# 13_MRAM_RTC_WDT.net
KiCad netlist of a schematic drawn in Altium Designer
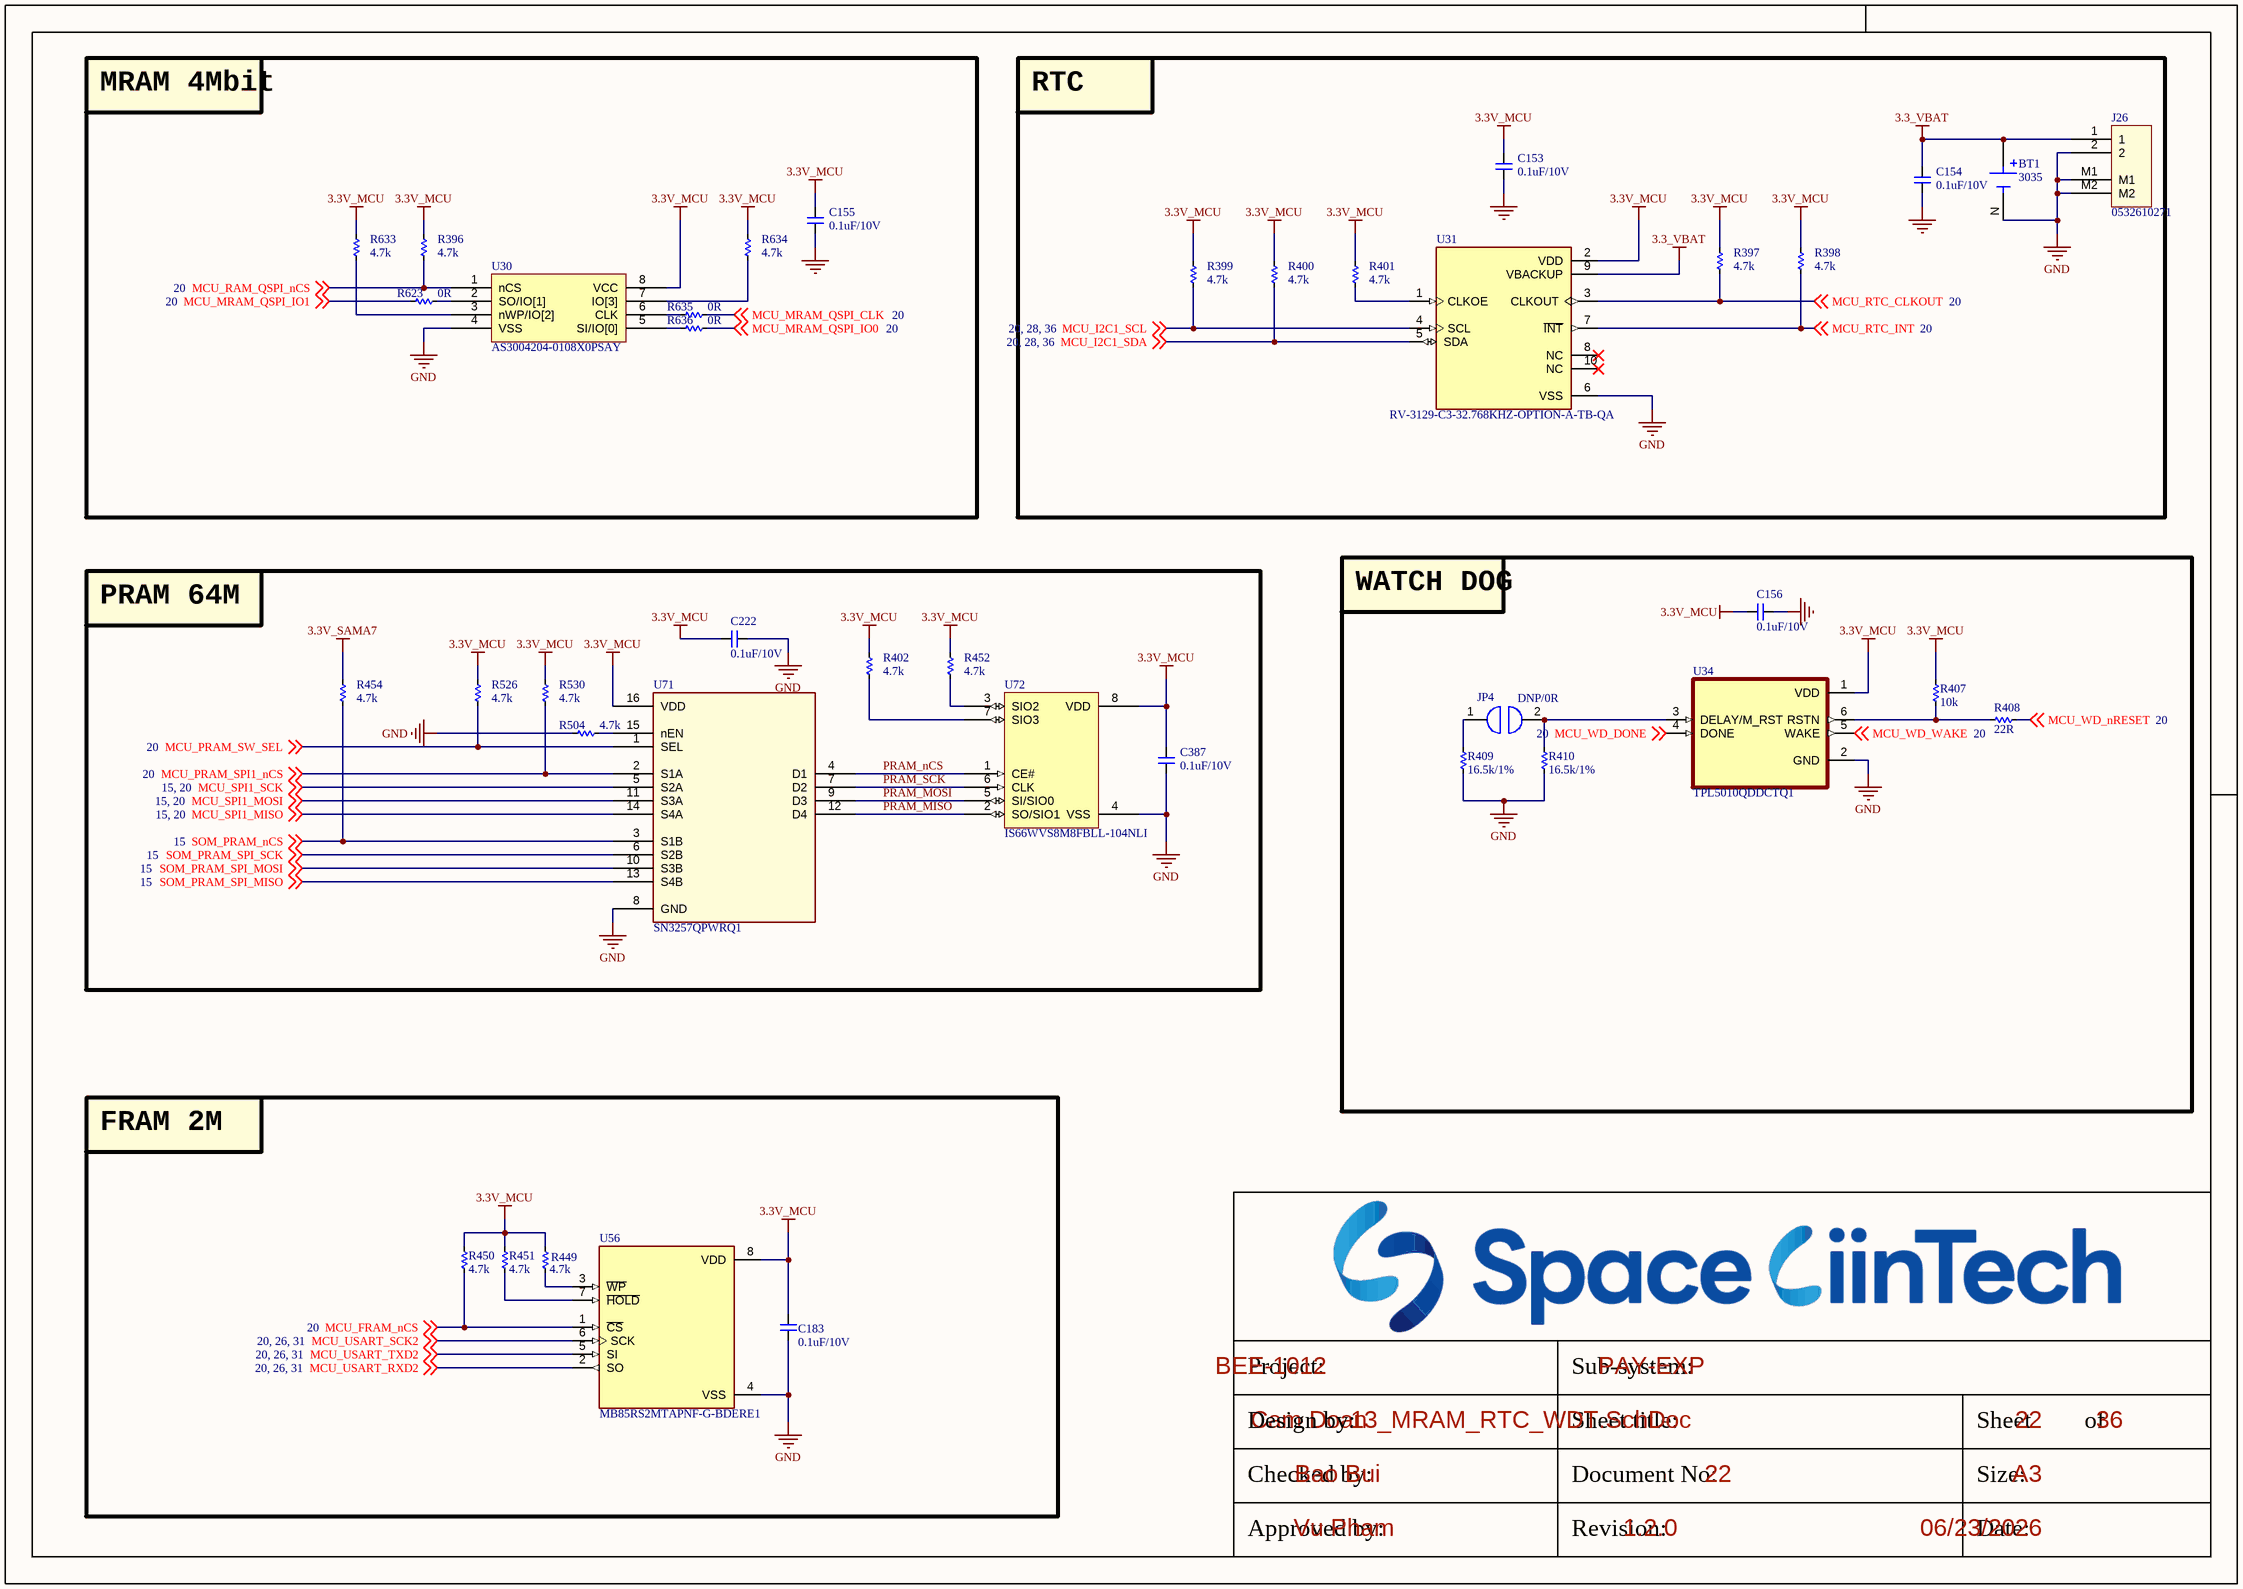
[diagram p0: 13_MRAM_RTC_WDT.SchDoc]

(export (version "E")
  (design (tool "Eeschema 10.0.6"))
  (components
    (comp (ref "BT1")
      (value "3035")
      (footprint "BAT_3035")
      (description "Battery Clip; THM; 20mm Cell; PhosBronze/Nickel ¦ Keystone Electronics 3035")
      (fields (field (name "MF") "Keystone Electronics"))
      (libsource (lib "LABLIB") (part "BT_HOLDER_3035"))
    )
    (comp (ref "C153")
      (value "0.1uF/10V")
      (footprint "CAP_C_1005X60")
      (description "CAP")
      (libsource (lib "LABLIB") (part "_CAP_C_2"))
    )
    (comp (ref "C154")
      (value "0.1uF/10V")
      (footprint "CAP_C_1005X60")
      (description "CAP")
      (libsource (lib "LABLIB") (part "_CAP_C_2"))
    )
    (comp (ref "C155")
      (value "0.1uF/10V")
      (footprint "CAP_C_1005X60")
      (description "CAP")
      (libsource (lib "LABLIB") (part "_CAP_C_2"))
    )
    (comp (ref "C156")
      (value "0.1uF/10V")
      (footprint "CAP_C_1005X60")
      (description "CAP")
      (libsource (lib "LABLIB") (part "_CAP_C_2"))
    )
    (comp (ref "C183")
      (value "0.1uF/10V")
      (footprint "CAP_C_1005X60")
      (description "CAP CHIP")
      (libsource (lib "LABLIB") (part "_CAP_C_2"))
    )
    (comp (ref "C222")
      (value "0.1uF/10V")
      (footprint "CAP_C_1005X60")
      (description "CAP")
      (libsource (lib "LABLIB") (part "_CAP_C_2"))
    )
    (comp (ref "C387")
      (value "0.1uF/10V")
      (footprint "CAP_C_1005X60")
      (description "CAP")
      (libsource (lib "LABLIB") (part "_CAP_C_2"))
    )
    (comp (ref "J26")
      (value "0532610271")
      (footprint "molex_0532610271")
      (libsource (lib "LABLIB") (part "Header 2x1_2M"))
    )
    (comp (ref "JP4") (value "DNP/0R") (footprint "JUMPER_1608") (libsource (lib "EXP_V1") (part "JUMPER")))
    (comp (ref "R396")
      (value "4.7k")
      (footprint "RES_C_1005X40")
      (description "RES")
      (libsource (lib "LABLIB") (part "_RES_B_2"))
    )
    (comp (ref "R397")
      (value "4.7k")
      (footprint "RES_C_1005X40")
      (description "RES")
      (libsource (lib "LABLIB") (part "_RES_B_2"))
    )
    (comp (ref "R398")
      (value "4.7k")
      (footprint "RES_C_1005X40")
      (description "RES")
      (libsource (lib "LABLIB") (part "_RES_B_2"))
    )
    (comp (ref "R399")
      (value "4.7k")
      (footprint "RES_C_1005X40")
      (description "RES")
      (libsource (lib "LABLIB") (part "_RES_B_2"))
    )
    (comp (ref "R400")
      (value "4.7k")
      (footprint "RES_C_1005X40")
      (description "RES")
      (libsource (lib "LABLIB") (part "_RES_B_2"))
    )
    (comp (ref "R401")
      (value "4.7k")
      (footprint "RES_C_1005X40")
      (description "RES")
      (libsource (lib "LABLIB") (part "_RES_B_2"))
    )
    (comp (ref "R402")
      (value "4.7k")
      (footprint "RES_C_1005X40")
      (description "RES")
      (libsource (lib "LABLIB") (part "_RES_B_2"))
    )
    (comp (ref "R407")
      (value "10k")
      (footprint "RES_C_1005X40")
      (description "RES")
      (libsource (lib "LABLIB") (part "_RES_B_2"))
    )
    (comp (ref "R408")
      (value "22R")
      (footprint "RES_C_1005X40")
      (description "RES")
      (libsource (lib "LABLIB") (part "_RES_B_2"))
    )
    (comp (ref "R409")
      (value "16.5k/1%")
      (footprint "RES_C_1005X40")
      (description "RES")
      (libsource (lib "LABLIB") (part "_RES_B_2"))
    )
    (comp (ref "R410")
      (value "16.5k/1%")
      (footprint "RES_C_1005X40")
      (description "RES")
      (libsource (lib "LABLIB") (part "_RES_B_2"))
    )
    (comp (ref "R449")
      (value "4.7k")
      (footprint "RES_C_1005X40")
      (description "RES")
      (libsource (lib "LABLIB") (part "_RES_B_2"))
    )
    (comp (ref "R450")
      (value "4.7k")
      (footprint "RES_C_1005X40")
      (description "RES")
      (libsource (lib "LABLIB") (part "_RES_B_2"))
    )
    (comp (ref "R451")
      (value "4.7k")
      (footprint "RES_C_1005X40")
      (description "RES")
      (libsource (lib "LABLIB") (part "_RES_B_2"))
    )
    (comp (ref "R452")
      (value "4.7k")
      (footprint "RES_C_1005X40")
      (description "RES")
      (libsource (lib "LABLIB") (part "_RES_B_2"))
    )
    (comp (ref "R454")
      (value "4.7k")
      (footprint "RES_C_1005X40")
      (description "RES")
      (libsource (lib "LABLIB") (part "_RES_B_2"))
    )
    (comp (ref "R504")
      (value "4.7k")
      (footprint "RES_C_1005X40")
      (description "RES")
      (libsource (lib "LABLIB") (part "_RES_B_2"))
    )
    (comp (ref "R526")
      (value "4.7k")
      (footprint "RES_C_1005X40")
      (description "RES")
      (libsource (lib "LABLIB") (part "_RES_B_2"))
    )
    (comp (ref "R530")
      (value "4.7k")
      (footprint "RES_C_1005X40")
      (description "RES")
      (libsource (lib "LABLIB") (part "_RES_B_2"))
    )
    (comp (ref "R623")
      (value "0R")
      (footprint "RES_C_1005X40")
      (description "RES")
      (libsource (lib "LABLIB") (part "_RES_B_2"))
    )
    (comp (ref "R633")
      (value "4.7k")
      (footprint "RES_C_1005X40")
      (description "RES")
      (libsource (lib "LABLIB") (part "_RES_B_2"))
    )
    (comp (ref "R634")
      (value "4.7k")
      (footprint "RES_C_1005X40")
      (description "RES")
      (libsource (lib "LABLIB") (part "_RES_B_2"))
    )
    (comp (ref "R635")
      (value "0R")
      (footprint "RES_C_1005X40")
      (description "RES")
      (libsource (lib "LABLIB") (part "_RES_B_2"))
    )
    (comp (ref "R636")
      (value "0R")
      (footprint "RES_C_1005X40")
      (description "RES")
      (libsource (lib "LABLIB") (part "_RES_B_2"))
    )
    (comp (ref "U30")
      (value "AS3004204-0108X0PSAY")
      (footprint "SOIC127P790X216-8")
      (libsource (lib "LABLIB") (part "IC_RAM_AS3004204-0108X0PSAY"))
    )
    (comp (ref "U31")
      (value "RV-3129-C3-32.768KHZ-OPTION-A-TB-QA")
      (footprint "IC_RV-3129-C3_32.768KHZ_OPTION_A_TB_QA")
      (description "Real-Time Clock Module, Temperature compensated, in 2.5 x 3.7 mm package")
      (fields (field (name "MF") "Micro Crystal") (field (name "MP") "RV-3129-C3 32.768KHZ OPTION A TB QA"))
      (libsource (lib "RV-3129-C3_32.768KHZ_OPTION_A_TB_QA") (part "RV-3129-C3_32.768KHZ_OPTION_A_TB_QA"))
    )
    (comp (ref "U34")
      (value "TPL5010QDDCTQ1")
      (footprint "SOT95P280X145-6N")
      (libsource (lib "TPL5010QDDCTQ1") (part "TPL5010QDDCTQ1"))
    )
    (comp (ref "U56")
      (value "MB85RS2MTAPNF-G-BDERE1")
      (footprint "SOIC127P602X173-8N")
      (description "FRAM _Ferroelectric RAM_ Memory IC 2Mb _256K x 8_ SPI 40MHz 8-SOP")
      (fields (field (name "MF") "Fujitsu Electronics") (field (name "DIGI-KEY_PART_NUMBER") "865-1286-1-ND"))
      (libsource (lib "MB85RS2MTAPNF-G-BDERE1") (part "MB85RS2MTAPNF-G-BDERE1"))
    )
    (comp (ref "U71")
      (value "SN3257QPWRQ1")
      (footprint "SOIC_PRQ1_TEX")
      (fields (field (name "COPYRIGHT") "Copyright (C) 2025 Ultra Librarian. All rights reserved."))
      (libsource (lib "LABLIB") (part "IC_SW_SPI_SN3257QPWRQ1"))
    )
    (comp (ref "U72")
      (value "IS66WVS8M8FBLL-104NLI")
      (footprint "SOIC8_150MIL_N_ISI")
      (description "No Description Available")
      (fields
        (field (name "MANUFACTURER_PART_NUMBER") "IS66WVS4M8BLL-104NLI")
        (field (name "COPYRIGHT") "Copyright (C) 2025 Ultra Librarian. All rights reserved.")
      )
      (libsource (lib "LABLIB") (part "IS66WVS4M8BLL-104NLI"))
    )
  )
  (nets
    (net (code "1") (name "/PRAM_MISO") (class "Default")
      (node (ref "U71") (pin "12") (pinfunction "D4_12") (pintype "passive"))
      (node (ref "U72") (pin "2") (pinfunction "SO/SIO1_2") (pintype "bidirectional"))
    )
    (net (code "2") (name "/PRAM_MOSI") (class "Default")
      (node (ref "U71") (pin "9") (pinfunction "D3_9") (pintype "passive"))
      (node (ref "U72") (pin "5") (pinfunction "SI/SIO0_5") (pintype "bidirectional"))
    )
    (net (code "3") (name "/PRAM_SCK") (class "Default")
      (node (ref "U71") (pin "7") (pinfunction "D2_7") (pintype "passive"))
      (node (ref "U72") (pin "6") (pinfunction "CLK_6") (pintype "input"))
    )
    (net (code "4") (name "/PRAM_nCS") (class "Default")
      (node (ref "U71") (pin "4") (pinfunction "D1_4") (pintype "passive"))
      (node (ref "U72") (pin "1") (pinfunction "CE#_1") (pintype "input"))
    )
    (net (code "5") (name "3.3V_MCU") (class "Default")
      (node (ref "C153") (pin "2") (pinfunction "2_2") (pintype "passive"))
      (node (ref "C155") (pin "2") (pinfunction "2_2") (pintype "passive"))
      (node (ref "C156") (pin "2") (pinfunction "2_2") (pintype "passive"))
      (node (ref "C183") (pin "2") (pinfunction "2_2") (pintype "passive"))
      (node (ref "C222") (pin "1") (pinfunction "1_1") (pintype "passive"))
      (node (ref "C387") (pin "1") (pinfunction "1_1") (pintype "passive"))
      (node (ref "R396") (pin "2") (pinfunction "2_2") (pintype "passive"))
      (node (ref "R397") (pin "2") (pinfunction "2_2") (pintype "passive"))
      (node (ref "R398") (pin "2") (pinfunction "2_2") (pintype "passive"))
      (node (ref "R399") (pin "2") (pinfunction "2_2") (pintype "passive"))
      (node (ref "R400") (pin "2") (pinfunction "2_2") (pintype "passive"))
      (node (ref "R401") (pin "1") (pinfunction "1_1") (pintype "passive"))
      (node (ref "R402") (pin "2") (pinfunction "2_2") (pintype "passive"))
      (node (ref "R407") (pin "2") (pinfunction "2_2") (pintype "passive"))
      (node (ref "R449") (pin "2") (pinfunction "2_2") (pintype "passive"))
      (node (ref "R450") (pin "2") (pinfunction "2_2") (pintype "passive"))
      (node (ref "R451") (pin "2") (pinfunction "2_2") (pintype "passive"))
      (node (ref "R452") (pin "2") (pinfunction "2_2") (pintype "passive"))
      (node (ref "R526") (pin "2") (pinfunction "2_2") (pintype "passive"))
      (node (ref "R530") (pin "2") (pinfunction "2_2") (pintype "passive"))
      (node (ref "R633") (pin "2") (pinfunction "2_2") (pintype "passive"))
      (node (ref "R634") (pin "2") (pinfunction "2_2") (pintype "passive"))
      (node (ref "U30") (pin "8") (pinfunction "VCC_8") (pintype "passive"))
      (node (ref "U31") (pin "2") (pinfunction "VDD_2") (pintype "power_in"))
      (node (ref "U34") (pin "1") (pinfunction "VDD_1") (pintype "power_in"))
      (node (ref "U56") (pin "8") (pinfunction "VDD_8") (pintype "power_in"))
      (node (ref "U71") (pin "16") (pinfunction "VDD_16") (pintype "passive"))
      (node (ref "U72") (pin "8") (pinfunction "VDD_8") (pintype "power_in"))
    )
    (net (code "6") (name "3.3V_SAMA7") (class "Default")
      (node (ref "R454") (pin "2") (pinfunction "2_2") (pintype "passive"))
    )
    (net (code "7") (name "3.3_VBAT") (class "Default")
      (node (ref "BT1") (pin "P1") (pinfunction "POS_P1") (pintype "passive"))
      (node (ref "BT1") (pin "P2") (pinfunction "POS_P2") (pintype "passive"))
      (node (ref "C154") (pin "2") (pinfunction "2_2") (pintype "passive"))
      (node (ref "J26") (pin "1") (pinfunction "1_1") (pintype "passive"))
      (node (ref "U31") (pin "9") (pinfunction "VBACKUP_9") (pintype "power_in"))
    )
    (net (code "8") (name "GND") (class "Default")
      (node (ref "BT1") (pin "N") (pinfunction "NEG_N") (pintype "passive"))
      (node (ref "C153") (pin "1") (pinfunction "1_1") (pintype "passive"))
      (node (ref "C154") (pin "1") (pinfunction "1_1") (pintype "passive"))
      (node (ref "C155") (pin "1") (pinfunction "1_1") (pintype "passive"))
      (node (ref "C156") (pin "1") (pinfunction "1_1") (pintype "passive"))
      (node (ref "C183") (pin "1") (pinfunction "1_1") (pintype "passive"))
      (node (ref "C222") (pin "2") (pinfunction "2_2") (pintype "passive"))
      (node (ref "C387") (pin "2") (pinfunction "2_2") (pintype "passive"))
      (node (ref "J26") (pin "2") (pinfunction "2_2") (pintype "passive"))
      (node (ref "J26") (pin "M1") (pinfunction "M1_M1") (pintype "passive"))
      (node (ref "J26") (pin "M2") (pinfunction "M2_M2") (pintype "passive"))
      (node (ref "R409") (pin "1") (pinfunction "1_1") (pintype "passive"))
      (node (ref "R410") (pin "1") (pinfunction "1_1") (pintype "passive"))
      (node (ref "R504") (pin "2") (pinfunction "2_2") (pintype "passive"))
      (node (ref "U30") (pin "4") (pinfunction "VSS_4") (pintype "passive"))
      (node (ref "U31") (pin "6") (pinfunction "VSS_6") (pintype "power_in"))
      (node (ref "U34") (pin "2") (pinfunction "GND_2") (pintype "power_in"))
      (node (ref "U56") (pin "4") (pinfunction "VSS_4") (pintype "power_in"))
      (node (ref "U71") (pin "8") (pinfunction "GND_8") (pintype "passive"))
      (node (ref "U72") (pin "4") (pinfunction "VSS_4") (pintype "power_in"))
    )
    (net (code "9") (name "MCU_FRAM_nCS") (class "Default")
      (node (ref "R450") (pin "1") (pinfunction "1_1") (pintype "passive"))
      (node (ref "U56") (pin "1") (pinfunction "~{CS}_1") (pintype "input"))
    )
    (net (code "10") (name "MCU_I2C1_SCL") (class "Default")
      (node (ref "R399") (pin "1") (pinfunction "1_1") (pintype "passive"))
      (node (ref "U31") (pin "4") (pinfunction "SCL_4") (pintype "input"))
    )
    (net (code "11") (name "MCU_I2C1_SDA") (class "Default")
      (node (ref "R400") (pin "1") (pinfunction "1_1") (pintype "passive"))
      (node (ref "U31") (pin "5") (pinfunction "SDA_5") (pintype "bidirectional"))
    )
    (net (code "12") (name "MCU_MRAM_QSPI_CLK") (class "Default")
      (node (ref "R635") (pin "1") (pinfunction "1_1") (pintype "passive"))
    )
    (net (code "13") (name "MCU_MRAM_QSPI_IO0") (class "Default")
      (node (ref "R636") (pin "1") (pinfunction "1_1") (pintype "passive"))
    )
    (net (code "14") (name "MCU_MRAM_QSPI_IO1") (class "Default")
      (node (ref "R623") (pin "2") (pinfunction "2_2") (pintype "passive"))
    )
    (net (code "15") (name "MCU_PRAM_SPI1_nCS") (class "Default")
      (node (ref "R530") (pin "1") (pinfunction "1_1") (pintype "passive"))
      (node (ref "U71") (pin "2") (pinfunction "S1A_2") (pintype "passive"))
    )
    (net (code "16") (name "MCU_PRAM_SW_SEL") (class "Default")
      (node (ref "R526") (pin "1") (pinfunction "1_1") (pintype "passive"))
      (node (ref "U71") (pin "1") (pinfunction "SEL_1") (pintype "passive"))
    )
    (net (code "17") (name "MCU_RAM_QSPI_nCS") (class "Default")
      (node (ref "R396") (pin "1") (pinfunction "1_1") (pintype "passive"))
      (node (ref "U30") (pin "1") (pinfunction "nCS_1") (pintype "passive"))
    )
    (net (code "18") (name "MCU_RTC_CLKOUT") (class "Default")
      (node (ref "R397") (pin "1") (pinfunction "1_1") (pintype "passive"))
      (node (ref "U31") (pin "3") (pinfunction "CLKOUT_3") (pintype "output"))
    )
    (net (code "19") (name "MCU_RTC_INT") (class "Default")
      (node (ref "R398") (pin "1") (pinfunction "1_1") (pintype "passive"))
      (node (ref "U31") (pin "7") (pinfunction "~{INT}_7") (pintype "output"))
    )
    (net (code "20") (name "MCU_SPI1_MISO") (class "Default")
      (node (ref "U71") (pin "14") (pinfunction "S4A_14") (pintype "passive"))
    )
    (net (code "21") (name "MCU_SPI1_MOSI") (class "Default")
      (node (ref "U71") (pin "11") (pinfunction "S3A_11") (pintype "passive"))
    )
    (net (code "22") (name "MCU_SPI1_SCK") (class "Default")
      (node (ref "U71") (pin "5") (pinfunction "S2A_5") (pintype "passive"))
    )
    (net (code "23") (name "MCU_USART_RXD2") (class "Default")
      (node (ref "U56") (pin "2") (pinfunction "SO_2") (pintype "output"))
    )
    (net (code "24") (name "MCU_USART_SCK2") (class "Default")
      (node (ref "U56") (pin "6") (pinfunction "SCK_6") (pintype "input"))
    )
    (net (code "25") (name "MCU_USART_TXD2") (class "Default")
      (node (ref "U56") (pin "5") (pinfunction "SI_5") (pintype "input"))
    )
    (net (code "26") (name "MCU_WD_DONE") (class "Default")
      (node (ref "U34") (pin "4") (pinfunction "DONE_4") (pintype "input"))
    )
    (net (code "27") (name "MCU_WD_WAKE") (class "Default")
      (node (ref "U34") (pin "5") (pinfunction "WAKE_5") (pintype "output"))
    )
    (net (code "28") (name "MCU_WD_nRESET") (class "Default")
      (node (ref "R408") (pin "1") (pinfunction "1_1") (pintype "passive"))
    )
    (net (code "29") (name "Net-(JP4-Pad1)") (class "Default")
      (node (ref "JP4") (pin "1") (pinfunction "1_1") (pintype "passive"))
      (node (ref "R409") (pin "2") (pinfunction "2_2") (pintype "passive"))
    )
    (net (code "30") (name "Net-(U30-CLK)") (class "Default")
      (node (ref "R635") (pin "2") (pinfunction "2_2") (pintype "passive"))
      (node (ref "U30") (pin "6") (pinfunction "CLK_6") (pintype "passive"))
    )
    (net (code "31") (name "Net-(U30-IO[3])") (class "Default")
      (node (ref "R634") (pin "1") (pinfunction "1_1") (pintype "passive"))
      (node (ref "U30") (pin "7") (pinfunction "IO[3]_7") (pintype "passive"))
    )
    (net (code "32") (name "Net-(U30-SI{slash}IO[0])") (class "Default")
      (node (ref "R636") (pin "2") (pinfunction "2_2") (pintype "passive"))
      (node (ref "U30") (pin "5") (pinfunction "SI/IO[0]_5") (pintype "passive"))
    )
    (net (code "33") (name "Net-(U30-SO{slash}IO[1])") (class "Default")
      (node (ref "R623") (pin "1") (pinfunction "1_1") (pintype "passive"))
      (node (ref "U30") (pin "2") (pinfunction "SO/IO[1]_2") (pintype "passive"))
    )
    (net (code "34") (name "Net-(U30-nWP{slash}IO[2])") (class "Default")
      (node (ref "R633") (pin "1") (pinfunction "1_1") (pintype "passive"))
      (node (ref "U30") (pin "3") (pinfunction "nWP/IO[2]_3") (pintype "passive"))
    )
    (net (code "35") (name "Net-(U31-CLKOE)") (class "Default")
      (node (ref "R401") (pin "2") (pinfunction "2_2") (pintype "passive"))
      (node (ref "U31") (pin "1") (pinfunction "CLKOE_1") (pintype "input"))
    )
    (net (code "36") (name "Net-(U34-DELAY{slash}M_RST)") (class "Default")
      (node (ref "JP4") (pin "2") (pinfunction "2_2") (pintype "passive"))
      (node (ref "R410") (pin "2") (pinfunction "2_2") (pintype "passive"))
      (node (ref "U34") (pin "3") (pinfunction "DELAY/M_RST_3") (pintype "input"))
    )
    (net (code "37") (name "Net-(U34-RSTN)") (class "Default")
      (node (ref "R407") (pin "1") (pinfunction "1_1") (pintype "passive"))
      (node (ref "R408") (pin "2") (pinfunction "2_2") (pintype "passive"))
      (node (ref "U34") (pin "6") (pinfunction "RSTN_6") (pintype "output"))
    )
    (net (code "38") (name "Net-(U56-~{HOLD})") (class "Default")
      (node (ref "R451") (pin "1") (pinfunction "1_1") (pintype "passive"))
      (node (ref "U56") (pin "7") (pinfunction "~{HOLD}_7") (pintype "input"))
    )
    (net (code "39") (name "Net-(U56-~{WP})") (class "Default")
      (node (ref "R449") (pin "1") (pinfunction "1_1") (pintype "passive"))
      (node (ref "U56") (pin "3") (pinfunction "~{WP}_3") (pintype "input"))
    )
    (net (code "40") (name "Net-(U71-nEN)") (class "Default")
      (node (ref "R504") (pin "1") (pinfunction "1_1") (pintype "passive"))
      (node (ref "U71") (pin "15") (pinfunction "nEN_15") (pintype "passive"))
    )
    (net (code "41") (name "Net-(U72-SIO2)") (class "Default")
      (node (ref "R452") (pin "1") (pinfunction "1_1") (pintype "passive"))
      (node (ref "U72") (pin "3") (pinfunction "SIO2_3") (pintype "bidirectional"))
    )
    (net (code "42") (name "Net-(U72-SIO3)") (class "Default")
      (node (ref "R402") (pin "1") (pinfunction "1_1") (pintype "passive"))
      (node (ref "U72") (pin "7") (pinfunction "SIO3_7") (pintype "bidirectional"))
    )
    (net (code "43") (name "SOM_PRAM_SPI_MISO") (class "Default")
      (node (ref "U71") (pin "13") (pinfunction "S4B_13") (pintype "passive"))
    )
    (net (code "44") (name "SOM_PRAM_SPI_MOSI") (class "Default")
      (node (ref "U71") (pin "10") (pinfunction "S3B_10") (pintype "passive"))
    )
    (net (code "45") (name "SOM_PRAM_SPI_SCK") (class "Default")
      (node (ref "U71") (pin "6") (pinfunction "S2B_6") (pintype "passive"))
    )
    (net (code "46") (name "SOM_PRAM_nCS") (class "Default")
      (node (ref "R454") (pin "1") (pinfunction "1_1") (pintype "passive"))
      (node (ref "U71") (pin "3") (pinfunction "S1B_3") (pintype "passive"))
    )
    (net (code "47") (name "unconnected-(U31-NC-Pad8)") (class "Default")
      (node (ref "U31") (pin "8") (pinfunction "NC_8") (pintype "passive+no_connect"))
    )
    (net (code "48") (name "unconnected-(U31-NC-Pad10)") (class "Default")
      (node (ref "U31") (pin "10") (pinfunction "NC_10") (pintype "passive+no_connect"))
    )
  )
)
